# Pl_clocksystem.net
KiCad netlist of a schematic drawn in Altium Designer
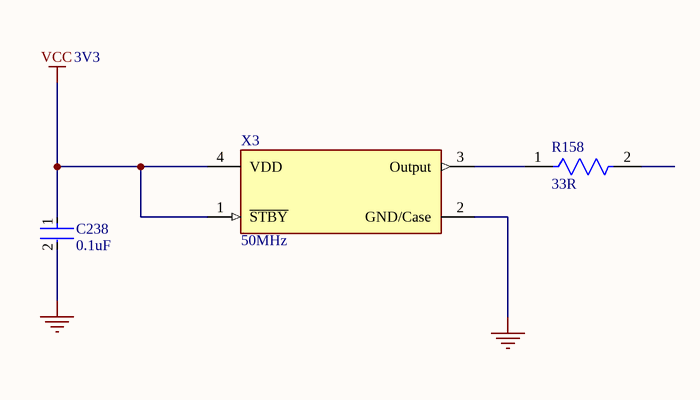
[diagram p0: Pl_clocksystem.SchDoc]

(export (version "E")
  (design (tool "Eeschema 10.0.6"))
  (components
    (comp (ref "C238")
      (value "0.1uF")
      (footprint "FP-C0402-BB-MFG")
      (description "C0402 0.10 μF X5R 10.00% 10 V")
      (fields (field (name "MANUFACTURER") "Kemet"))
      (libsource (lib "Altium Content Vault") (part "b4654b650e69147ec39a6b967a45e02"))
    )
    (comp (ref "R158")
      (value "33R")
      (footprint "FP-CRCW0603-e3-IPC_A")
      (description "RES Thick Film, 33Ω, 1%, 0.1W, 100ppm/°C, 0603")
      (fields (field (name "TOLERANCE") "1%"))
      (libsource (lib "Altium Content Vault") (part "1029c3af85768c4190bb7ad29bc67b5"))
    )
    (comp (ref "X3")
      (value "50MHz")
      (footprint "FP-ASE-MFG")
      (description "XTAL Oscillator 50MHz ±50ppm CMOS 3.3V 4-SMD 3.2mm x 2.5mm")
      (libsource (lib "Altium Content Vault") (part "61a724e6190563596ac712fef61ad37"))
    )
  )
  (nets
    (net (code "1") (name "<NO NET>") (class "Default")
      (node (ref "C238") (pin "2") (pinfunction "2_2") (pintype "passive"))
      (node (ref "X3") (pin "2") (pinfunction "GND/Case_2") (pintype "power_in"))
    )
    (net (code "2") (name "Net-(X3-Output)") (class "Default")
      (node (ref "R158") (pin "1") (pinfunction "1_1") (pintype "passive"))
      (node (ref "X3") (pin "3") (pinfunction "Output_3") (pintype "output"))
    )
    (net (code "3") (name "VCC") (class "Default")
      (node (ref "C238") (pin "1") (pinfunction "1_1") (pintype "passive"))
      (node (ref "X3") (pin "1") (pinfunction "~{STBY}_1") (pintype "input"))
      (node (ref "X3") (pin "4") (pinfunction "VDD_4") (pintype "power_in"))
    )
    (net (code "4") (name "unconnected-(R158-Pad2)") (class "Default")
      (node (ref "R158") (pin "2") (pinfunction "2_2") (pintype "passive"))
    )
  )
)
